# ASD2205.net
KiCad netlist of a schematic drawn in EAGLE
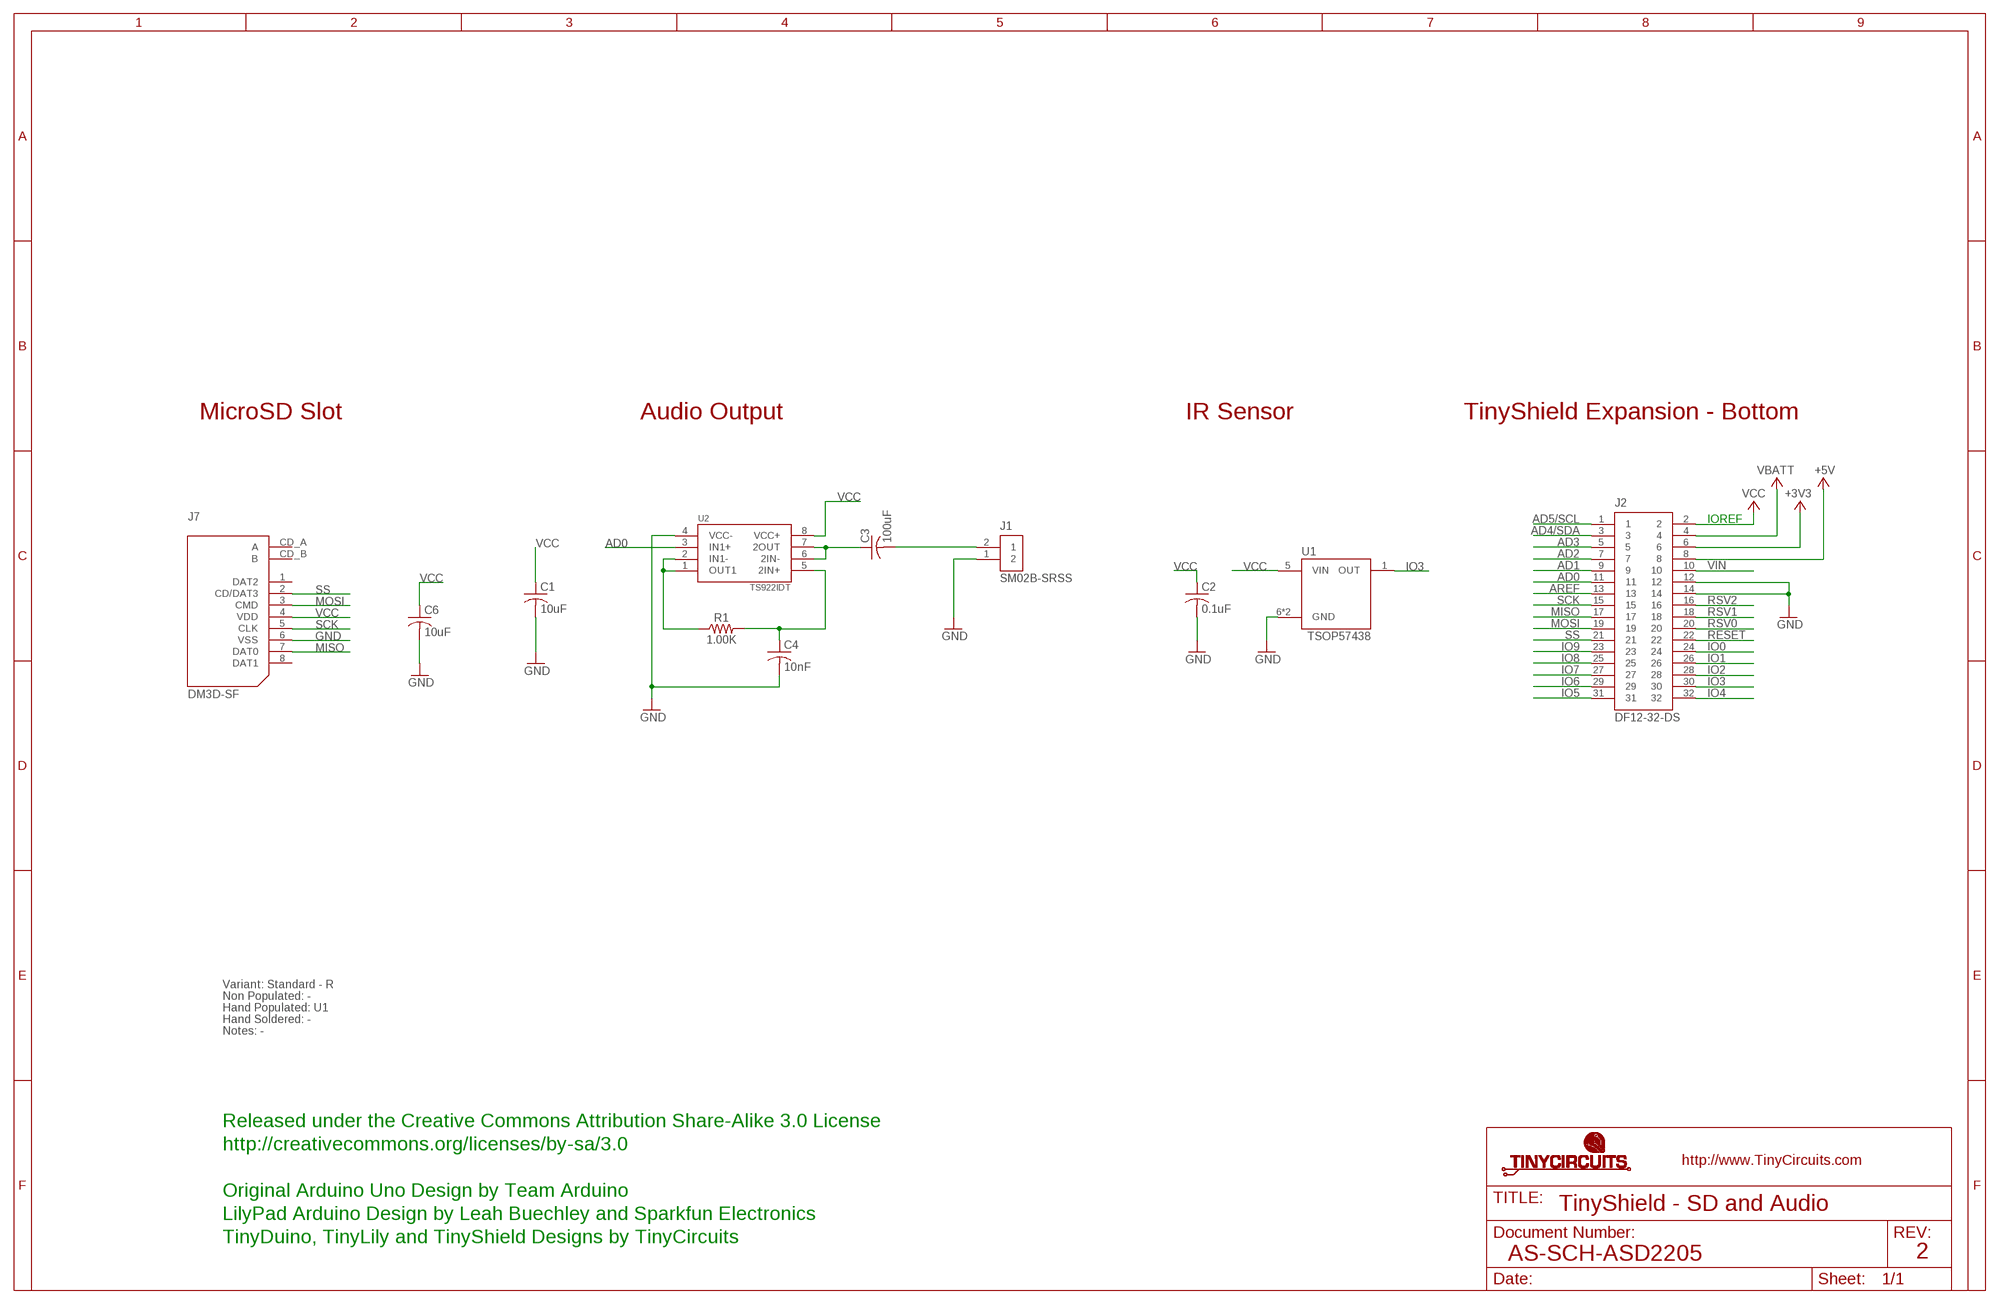
[diagram p0: schematic, sheet 1]

(export (version "E")
  (design (tool "Eeschema 10.0.6"))
  (components
    (comp (ref "C1")
      (value "10uF")
      (footprint "eagle-import:C0603")
      (fields (field (name "PARTNO") "AS-ITM-00002") (field (name "PARTNO_1") "AS-ITM-00002"))
      (libsource (lib "eagle-import") (part "AS-ITM-00002"))
    )
    (comp (ref "C2")
      (value "0.1uF")
      (footprint "eagle-import:C0402")
      (fields (field (name "PARTNO") "AS-ITM-00008"))
      (libsource (lib "eagle-import") (part "AS-ITM-00008"))
    )
    (comp (ref "C3")
      (value "100uF")
      (footprint "eagle-import:C1206")
      (fields (field (name "PARTNO") "AS-ITM-00095"))
      (libsource (lib "eagle-import") (part "AS-ITM-00095"))
    )
    (comp (ref "C4")
      (value "10nF")
      (footprint "eagle-import:C0402")
      (fields (field (name "PARTNO") "AS-ITM-00084"))
      (libsource (lib "eagle-import") (part "AS-ITM-00084"))
    )
    (comp (ref "C6")
      (value "10uF")
      (footprint "eagle-import:C0603")
      (fields (field (name "PARTNO") "AS-ITM-00002"))
      (libsource (lib "eagle-import") (part "AS-ITM-00002"))
    )
    (comp (ref "J1")
      (value "SM02B-SRSS")
      (footprint "eagle-import:JST_SH_2X1")
      (fields (field (name "PARTNO") "AS-ITM-00231"))
      (libsource (lib "eagle-import") (part "AS-ITM-00231"))
    )
    (comp (ref "J2")
      (value "DF12-32-DS")
      (footprint "eagle-import:DF12-32-DS")
      (fields (field (name "PARTNO") "AS-ITM-00012") (field (name "PARTNO_1") "AS-ITM-00012"))
      (libsource (lib "eagle-import") (part "AS-ITM-00012"))
    )
    (comp (ref "J7")
      (value "DM3D-SF")
      (footprint "eagle-import:SD_CARD")
      (fields (field (name "PARTNO") "AS-ITM-00047"))
      (libsource (lib "eagle-import") (part "AS-ITM-00047"))
    )
    (comp (ref "R1")
      (value "1.00K")
      (footprint "eagle-import:0402")
      (fields (field (name "PARTNO") "AS-ITM-00003") (field (name "PARTNO_1") "AS-ITM-00003"))
      (libsource (lib "eagle-import") (part "AS-ITM-00003"))
    )
    (comp (ref "U1")
      (value "TSOP57438")
      (footprint "eagle-import:TSOP57")
      (fields (field (name "PARTNO") "AS-ITM-00360"))
      (libsource (lib "eagle-import") (part "AS-ITM-00360"))
    )
    (comp (ref "U2")
      (value "TS922IDT")
      (footprint "eagle-import:SO-08-COMPACT")
      (fields (field (name "PARTNO") "AS-ITM-00092"))
      (libsource (lib "eagle-import") (part "AS-ITM-000922"))
    )
  )
  (nets
    (net (code "1") (name "+3V3") (class "Default")
      (node (ref "J2") (pin "6") (pinfunction "6_6") (pintype "bidirectional"))
    )
    (net (code "2") (name "+5V") (class "Default")
      (node (ref "J2") (pin "8") (pinfunction "8_8") (pintype "bidirectional"))
    )
    (net (code "3") (name "/AD0") (class "Default")
      (node (ref "J2") (pin "11") (pinfunction "11_11") (pintype "bidirectional"))
      (node (ref "U2") (pin "3") (pinfunction "IN1+_3") (pintype "bidirectional"))
    )
    (net (code "4") (name "/AD1") (class "Default")
      (node (ref "J2") (pin "9") (pinfunction "9_9") (pintype "bidirectional"))
    )
    (net (code "5") (name "/AD2") (class "Default")
      (node (ref "J2") (pin "7") (pinfunction "7_7") (pintype "bidirectional"))
    )
    (net (code "6") (name "/AD3") (class "Default")
      (node (ref "J2") (pin "5") (pinfunction "5_5") (pintype "bidirectional"))
    )
    (net (code "7") (name "/AD4{slash}SDA") (class "Default")
      (node (ref "J2") (pin "3") (pinfunction "3_3") (pintype "bidirectional"))
    )
    (net (code "8") (name "/AD5{slash}SCL") (class "Default")
      (node (ref "J2") (pin "1") (pinfunction "1_1") (pintype "bidirectional"))
    )
    (net (code "9") (name "/AREF") (class "Default")
      (node (ref "J2") (pin "13") (pinfunction "13_13") (pintype "bidirectional"))
    )
    (net (code "10") (name "/IO0") (class "Default")
      (node (ref "J2") (pin "24") (pinfunction "24_24") (pintype "bidirectional"))
    )
    (net (code "11") (name "/IO1") (class "Default")
      (node (ref "J2") (pin "26") (pinfunction "26_26") (pintype "bidirectional"))
    )
    (net (code "12") (name "/IO2") (class "Default")
      (node (ref "J2") (pin "28") (pinfunction "28_28") (pintype "bidirectional"))
    )
    (net (code "13") (name "/IO3") (class "Default")
      (node (ref "J2") (pin "30") (pinfunction "30_30") (pintype "bidirectional"))
      (node (ref "U1") (pin "1") (pinfunction "OUT_1") (pintype "bidirectional"))
    )
    (net (code "14") (name "/IO4") (class "Default")
      (node (ref "J2") (pin "32") (pinfunction "32_32") (pintype "bidirectional"))
    )
    (net (code "15") (name "/IO5") (class "Default")
      (node (ref "J2") (pin "31") (pinfunction "31_31") (pintype "bidirectional"))
    )
    (net (code "16") (name "/IO6") (class "Default")
      (node (ref "J2") (pin "29") (pinfunction "29_29") (pintype "bidirectional"))
    )
    (net (code "17") (name "/IO7") (class "Default")
      (node (ref "J2") (pin "27") (pinfunction "27_27") (pintype "bidirectional"))
    )
    (net (code "18") (name "/IO8") (class "Default")
      (node (ref "J2") (pin "25") (pinfunction "25_25") (pintype "bidirectional"))
    )
    (net (code "19") (name "/IO9") (class "Default")
      (node (ref "J2") (pin "23") (pinfunction "23_23") (pintype "bidirectional"))
    )
    (net (code "20") (name "/MISO") (class "Default")
      (node (ref "J2") (pin "17") (pinfunction "17_17") (pintype "bidirectional"))
      (node (ref "J7") (pin "7") (pinfunction "DAT0_7") (pintype "bidirectional"))
    )
    (net (code "21") (name "/MOSI") (class "Default")
      (node (ref "J2") (pin "19") (pinfunction "19_19") (pintype "bidirectional"))
      (node (ref "J7") (pin "3") (pinfunction "CMD_3") (pintype "bidirectional"))
    )
    (net (code "22") (name "/RESET") (class "Default")
      (node (ref "J2") (pin "22") (pinfunction "22_22") (pintype "bidirectional"))
    )
    (net (code "23") (name "/RSV0") (class "Default")
      (node (ref "J2") (pin "20") (pinfunction "20_20") (pintype "bidirectional"))
    )
    (net (code "24") (name "/RSV1") (class "Default")
      (node (ref "J2") (pin "18") (pinfunction "18_18") (pintype "bidirectional"))
    )
    (net (code "25") (name "/RSV2") (class "Default")
      (node (ref "J2") (pin "16") (pinfunction "16_16") (pintype "bidirectional"))
    )
    (net (code "26") (name "/SCK") (class "Default")
      (node (ref "J2") (pin "15") (pinfunction "15_15") (pintype "bidirectional"))
      (node (ref "J7") (pin "5") (pinfunction "CLK_5") (pintype "bidirectional"))
    )
    (net (code "27") (name "/SS") (class "Default")
      (node (ref "J2") (pin "21") (pinfunction "21_21") (pintype "bidirectional"))
      (node (ref "J7") (pin "2") (pinfunction "CD/DAT3_2") (pintype "bidirectional"))
    )
    (net (code "28") (name "/VIN") (class "Default")
      (node (ref "J2") (pin "10") (pinfunction "10_10") (pintype "bidirectional"))
    )
    (net (code "29") (name "GND") (class "Default")
      (node (ref "C1") (pin "2") (pinfunction "2_2") (pintype "passive"))
      (node (ref "C2") (pin "2") (pinfunction "2_2") (pintype "passive"))
      (node (ref "C4") (pin "2") (pinfunction "2_2") (pintype "passive"))
      (node (ref "C6") (pin "2") (pinfunction "2_2") (pintype "passive"))
      (node (ref "J1") (pin "1") (pinfunction "2_1") (pintype "bidirectional"))
      (node (ref "J2") (pin "12") (pinfunction "12_12") (pintype "bidirectional"))
      (node (ref "J2") (pin "14") (pinfunction "14_14") (pintype "bidirectional"))
      (node (ref "J7") (pin "6") (pinfunction "VSS_6") (pintype "bidirectional"))
      (node (ref "U1") (pin "6") (pinfunction "GND_6") (pintype "bidirectional"))
      (node (ref "U1") (pin "8") (pinfunction "GND_8") (pintype "bidirectional"))
      (node (ref "U2") (pin "4") (pinfunction "VCC-_4") (pintype "bidirectional"))
    )
    (net (code "30") (name "Net-(J1-1)") (class "Default")
      (node (ref "C3") (pin "2") (pinfunction "2_2") (pintype "passive"))
      (node (ref "J1") (pin "2") (pinfunction "1_2") (pintype "bidirectional"))
    )
    (net (code "31") (name "Net-(U2-2IN+)") (class "Default")
      (node (ref "C4") (pin "1") (pinfunction "1_1") (pintype "passive"))
      (node (ref "R1") (pin "2") (pinfunction "2_2") (pintype "passive"))
      (node (ref "U2") (pin "5") (pinfunction "2IN+_5") (pintype "bidirectional"))
    )
    (net (code "32") (name "Net-(U2-2IN-)") (class "Default")
      (node (ref "C3") (pin "1") (pinfunction "1_1") (pintype "passive"))
      (node (ref "U2") (pin "6") (pinfunction "2IN-_6") (pintype "bidirectional"))
      (node (ref "U2") (pin "7") (pinfunction "2OUT_7") (pintype "bidirectional"))
    )
    (net (code "33") (name "Net-(U2-IN1-)") (class "Default")
      (node (ref "R1") (pin "1") (pinfunction "1_1") (pintype "passive"))
      (node (ref "U2") (pin "1") (pinfunction "OUT1_1") (pintype "bidirectional"))
      (node (ref "U2") (pin "2") (pinfunction "IN1-_2") (pintype "bidirectional"))
    )
    (net (code "34") (name "VBATT") (class "Default")
      (node (ref "J2") (pin "4") (pinfunction "4_4") (pintype "bidirectional"))
    )
    (net (code "35") (name "VCC") (class "Default")
      (node (ref "C1") (pin "1") (pinfunction "1_1") (pintype "passive"))
      (node (ref "C2") (pin "1") (pinfunction "1_1") (pintype "passive"))
      (node (ref "C6") (pin "1") (pinfunction "1_1") (pintype "passive"))
      (node (ref "J2") (pin "2") (pinfunction "2_2") (pintype "bidirectional"))
      (node (ref "J7") (pin "4") (pinfunction "VDD_4") (pintype "bidirectional"))
      (node (ref "U1") (pin "5") (pinfunction "VIN_5") (pintype "bidirectional"))
      (node (ref "U2") (pin "8") (pinfunction "VCC+_8") (pintype "bidirectional"))
    )
    (net (code "36") (name "unconnected-(J7-A-PadCD_A)") (class "Default")
      (node (ref "J7") (pin "CD_A") (pinfunction "A_CD_A") (pintype "bidirectional"))
    )
    (net (code "37") (name "unconnected-(J7-B-PadCD_B)") (class "Default")
      (node (ref "J7") (pin "CD_B") (pinfunction "B_CD_B") (pintype "bidirectional"))
    )
    (net (code "38") (name "unconnected-(J7-DAT1-Pad8)") (class "Default")
      (node (ref "J7") (pin "8") (pinfunction "DAT1_8") (pintype "bidirectional"))
    )
    (net (code "39") (name "unconnected-(J7-DAT2-Pad1)") (class "Default")
      (node (ref "J7") (pin "1") (pinfunction "DAT2_1") (pintype "bidirectional"))
    )
  )
)
